# untitled.net
KiCad netlist of a schematic drawn in EAGLE
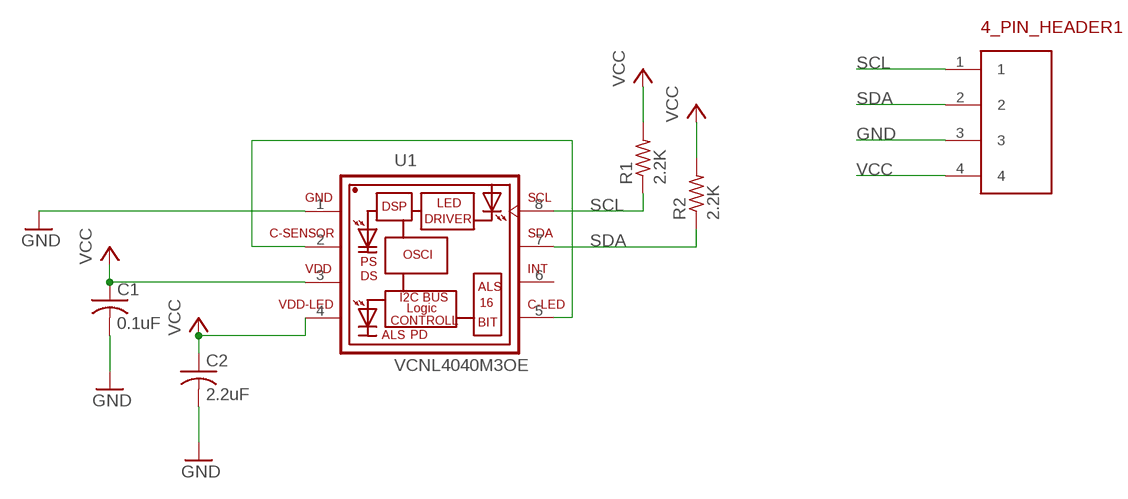
[diagram p0: schematic, sheet 1]

(export (version "E")
  (design (tool "Eeschema 10.0.6"))
  (components
    (comp (ref "4_PIN_HEADER1")
      (value "4_PIN_HEADER")
      (footprint "eagle-import:4_PIN_HEADER")
      (libsource (lib "eagle-import") (part "4_PIN_HEADER"))
    )
    (comp (ref "C1")
      (value "0.1uF")
      (footprint "eagle-import:C0201")
      (libsource (lib "eagle-import") (part "C_0201"))
    )
    (comp (ref "C2")
      (value "2.2uF")
      (footprint "eagle-import:C0201")
      (libsource (lib "eagle-import") (part "C_0201"))
    )
    (comp (ref "R1")
      (value "2.2K")
      (footprint "eagle-import:R0201")
      (libsource (lib "eagle-import") (part "R_0201"))
    )
    (comp (ref "R2")
      (value "2.2K")
      (footprint "eagle-import:R0201")
      (libsource (lib "eagle-import") (part "R_0201"))
    )
    (comp (ref "U1")
      (value "VCNL4040M3OE")
      (footprint "eagle-import:VISHAY_VCNL4040_4X2X1.1")
      (fields (field (name "MF") "Vishay"))
      (libsource (lib "eagle-import") (part "VCNL4040M3OE"))
    )
  )
  (nets
    (net (code "1") (name "/SCL") (class "Default")
      (node (ref "4_PIN_HEADER1") (pin "1") (pinfunction "1_1") (pintype "bidirectional"))
      (node (ref "R1") (pin "1") (pinfunction "1_1") (pintype "passive"))
      (node (ref "U1") (pin "8") (pinfunction "SCL_8") (pintype "input"))
    )
    (net (code "2") (name "/SDA") (class "Default")
      (node (ref "4_PIN_HEADER1") (pin "2") (pinfunction "2_2") (pintype "bidirectional"))
      (node (ref "R2") (pin "1") (pinfunction "1_1") (pintype "passive"))
      (node (ref "U1") (pin "7") (pinfunction "SDA_7") (pintype "bidirectional"))
    )
    (net (code "3") (name "GND") (class "Default")
      (node (ref "4_PIN_HEADER1") (pin "3") (pinfunction "3_3") (pintype "bidirectional"))
      (node (ref "C1") (pin "2") (pinfunction "2_2") (pintype "passive"))
      (node (ref "C2") (pin "2") (pinfunction "2_2") (pintype "passive"))
      (node (ref "U1") (pin "1") (pinfunction "GND_1") (pintype "power_in"))
    )
    (net (code "4") (name "Net-(U1-C-LED)") (class "Default")
      (node (ref "U1") (pin "2") (pinfunction "C-SENSOR_2") (pintype "output"))
      (node (ref "U1") (pin "5") (pinfunction "C-LED_5") (pintype "output"))
    )
    (net (code "5") (name "VCC") (class "Default")
      (node (ref "4_PIN_HEADER1") (pin "4") (pinfunction "4_4") (pintype "bidirectional"))
      (node (ref "C1") (pin "1") (pinfunction "1_1") (pintype "passive"))
      (node (ref "C2") (pin "1") (pinfunction "1_1") (pintype "passive"))
      (node (ref "R1") (pin "2") (pinfunction "2_2") (pintype "passive"))
      (node (ref "R2") (pin "2") (pinfunction "2_2") (pintype "passive"))
      (node (ref "U1") (pin "3") (pinfunction "VDD_3") (pintype "power_in"))
      (node (ref "U1") (pin "4") (pinfunction "VDD-LED_4") (pintype "power_in"))
    )
    (net (code "6") (name "unconnected-(U1-INT-Pad6)") (class "Default")
      (node (ref "U1") (pin "6") (pinfunction "INT_6") (pintype "output"))
    )
  )
)
